# giant-poe-pixel-controller-v1.net
KiCad netlist of a schematic drawn in EAGLE
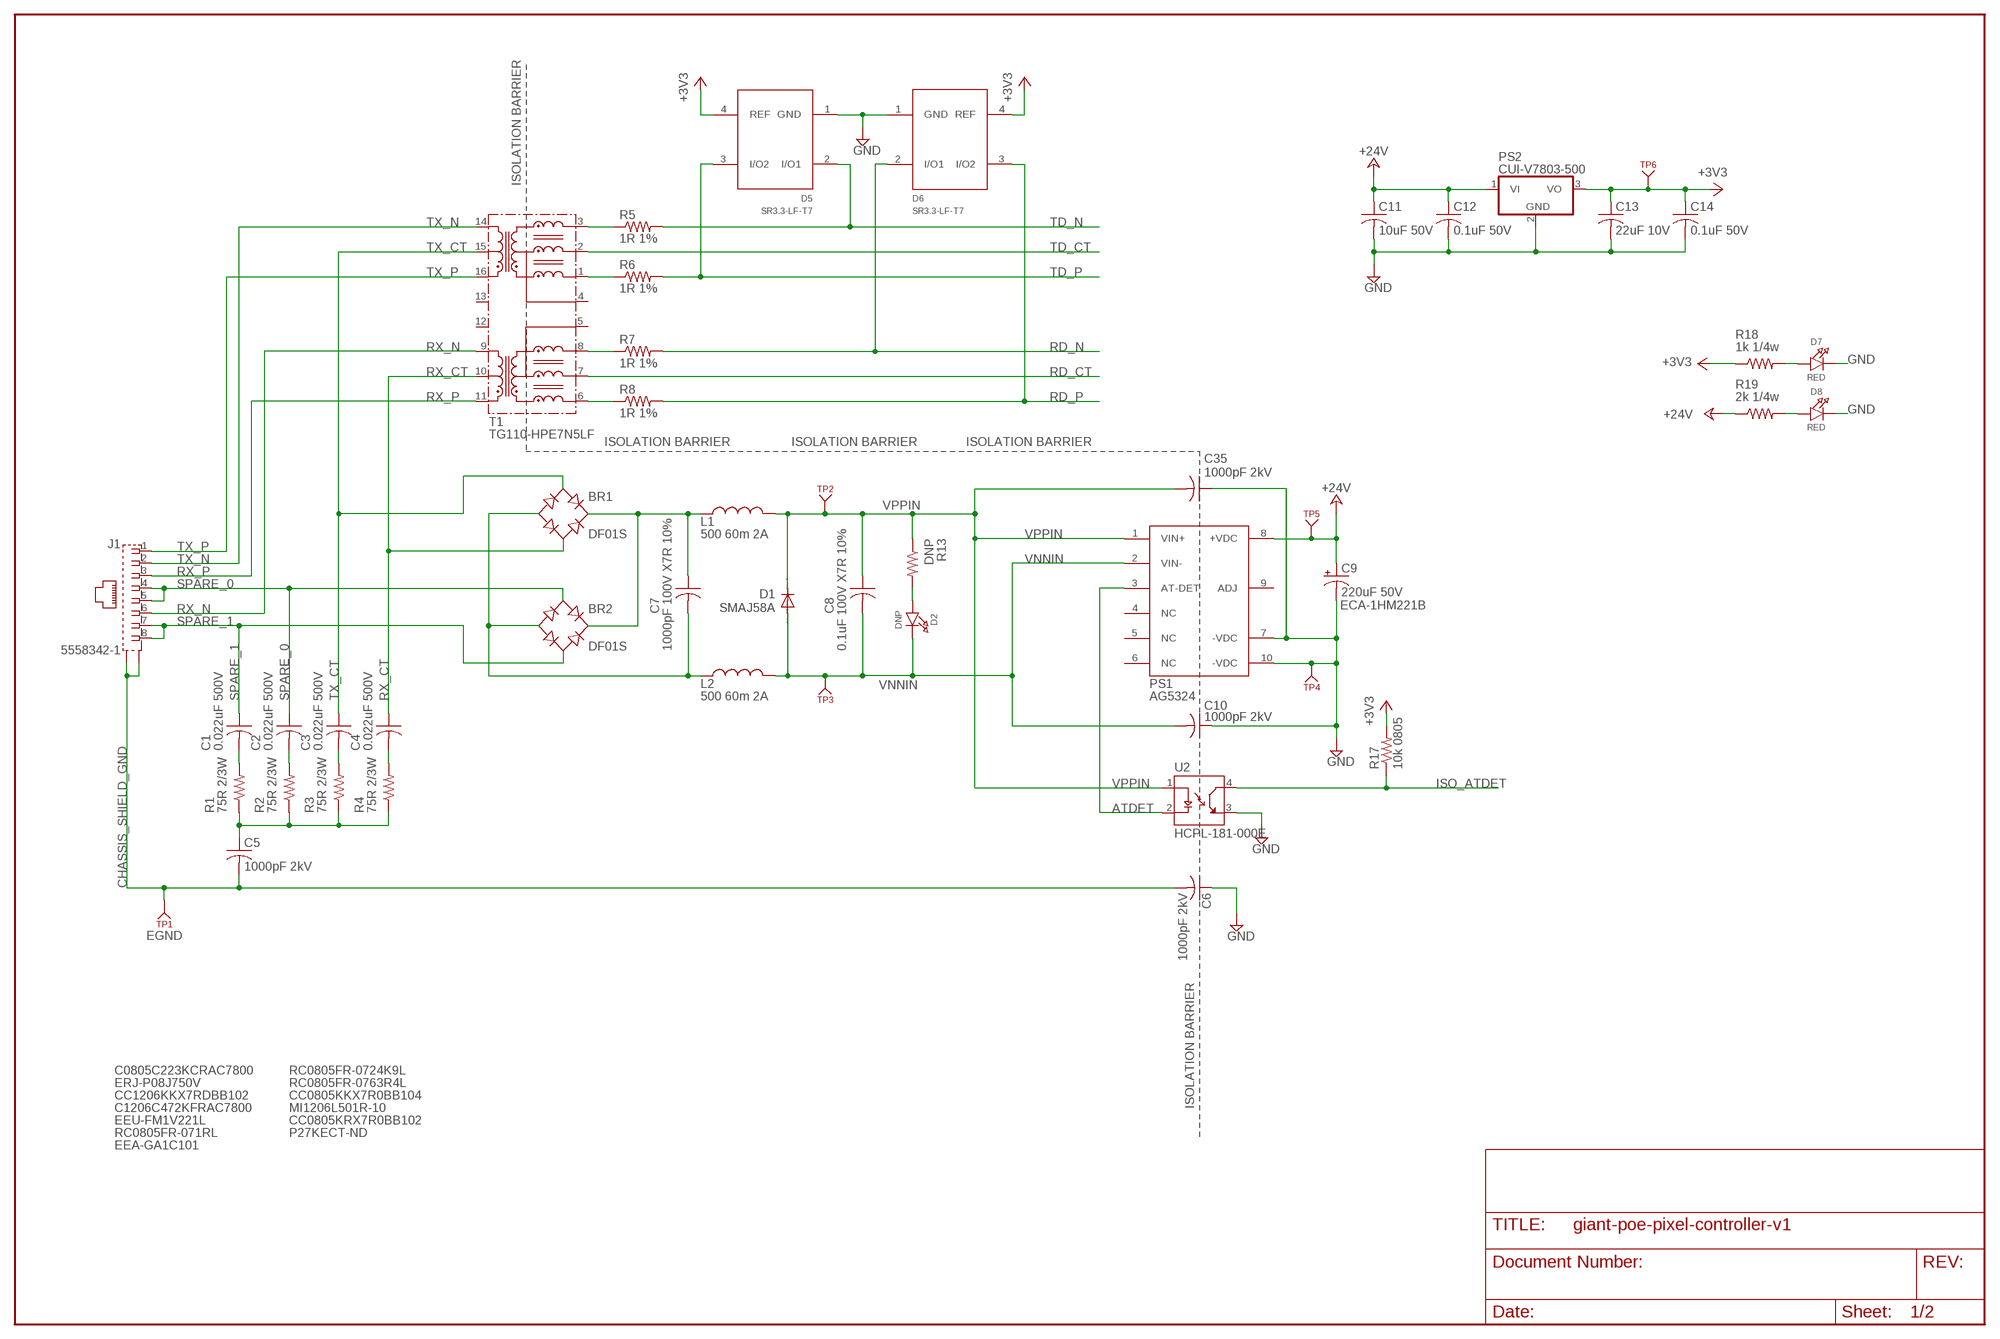
[diagram p0: schematic, sheet 1]
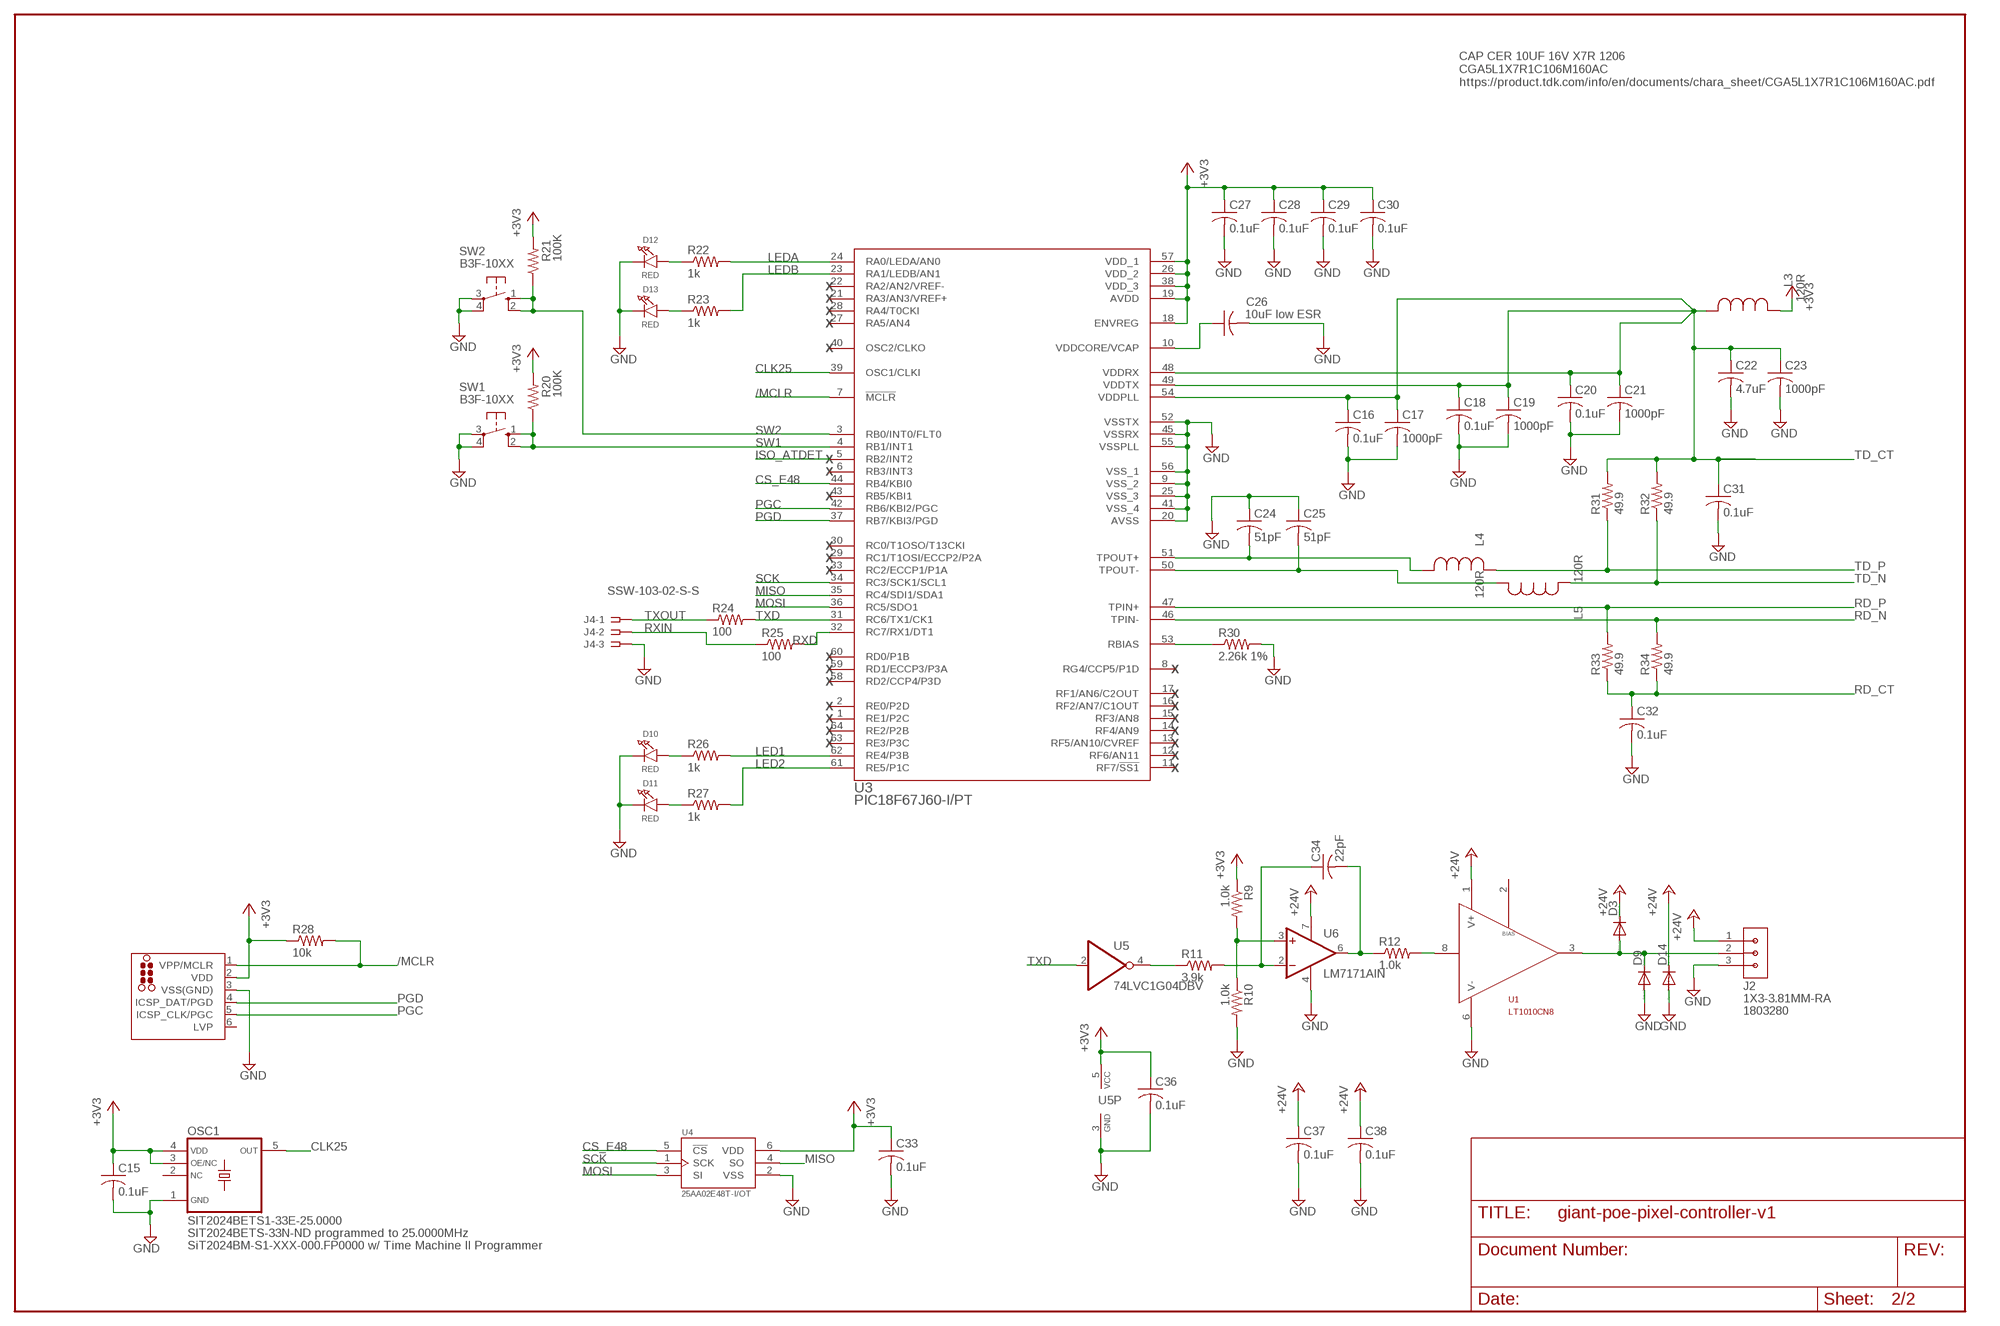
[diagram p1: schematic, sheet 2]

(export (version "E")
  (design (tool "Eeschema 10.0.6"))
  (components
    (comp (ref "BR1")
      (value "DF01S")
      (footprint "eagle-import:DFS")
      (libsource (lib "eagle-import") (part "DFS01"))
    )
    (comp (ref "BR2")
      (value "DF01S")
      (footprint "eagle-import:DFS")
      (libsource (lib "eagle-import") (part "DFS01"))
    )
    (comp (ref "C1")
      (value "0.022uF 500V")
      (footprint "eagle-import:C1206")
      (libsource (lib "eagle-import") (part "C-USC1206"))
    )
    (comp (ref "C2")
      (value "0.022uF 500V")
      (footprint "eagle-import:C1206")
      (libsource (lib "eagle-import") (part "C-USC1206"))
    )
    (comp (ref "C3")
      (value "0.022uF 500V")
      (footprint "eagle-import:C1206")
      (libsource (lib "eagle-import") (part "C-USC1206"))
    )
    (comp (ref "C4")
      (value "0.022uF 500V")
      (footprint "eagle-import:C1206")
      (libsource (lib "eagle-import") (part "C-USC1206"))
    )
    (comp (ref "C5")
      (value "1000pF 2kV")
      (footprint "eagle-import:C1206K")
      (libsource (lib "eagle-import") (part "C-USC1206K"))
    )
    (comp (ref "C6")
      (value "1000pF 2kV")
      (footprint "eagle-import:C1206K")
      (libsource (lib "eagle-import") (part "C-USC1206K"))
    )
    (comp (ref "C7")
      (value "1000pF 100V X7R 10%")
      (footprint "eagle-import:C0805")
      (libsource (lib "eagle-import") (part "C-USC0805"))
    )
    (comp (ref "C8")
      (value "0.1uF 100V X7R 10%")
      (footprint "eagle-import:C0805")
      (libsource (lib "eagle-import") (part "C-USC0805"))
    )
    (comp (ref "C9")
      (value "220uF 50V")
      (footprint "eagle-import:E5-10,5")
      (libsource (lib "eagle-import") (part "CPOL-USE5-10.5"))
    )
    (comp (ref "C10")
      (value "1000pF 2kV")
      (footprint "eagle-import:C1206K")
      (libsource (lib "eagle-import") (part "C-USC1206K"))
    )
    (comp (ref "C11")
      (value "10uF 50V")
      (footprint "eagle-import:C1210K")
      (fields (field (name "MFR") "KEMET") (field (name "MFR_PART_NO") "C1210C106K5RACTU"))
      (libsource (lib "eagle-import") (part "C-USC1210K"))
    )
    (comp (ref "C12")
      (value "0.1uF 50V")
      (footprint "eagle-import:C0805")
      (fields (field (name "MFR") "KEMET") (field (name "MFR_PART_NO") "C1206S104M5RACTU"))
      (libsource (lib "eagle-import") (part "C-USC0805"))
    )
    (comp (ref "C13")
      (value "22uF 10V")
      (footprint "eagle-import:C1206K")
      (fields (field (name "MFR") "KEMET") (field (name "MFR_PART_NO") "C1206C226K8RAC7800"))
      (libsource (lib "eagle-import") (part "C-USC1206K"))
    )
    (comp (ref "C14")
      (value "0.1uF 50V")
      (footprint "eagle-import:C0805")
      (fields (field (name "MFR") "KEMET") (field (name "MFR_PART_NO") "C1206S104M5RACTU"))
      (libsource (lib "eagle-import") (part "C-USC0805"))
    )
    (comp (ref "C35")
      (value "1000pF 2kV")
      (footprint "eagle-import:C1206K")
      (libsource (lib "eagle-import") (part "C-USC1206K"))
    )
    (comp (ref "D1")
      (value "SMAJ58A")
      (footprint "eagle-import:DO214AC")
      (libsource (lib "eagle-import") (part "DIODE-DO214AC"))
    )
    (comp (ref "D2")
      (value "DNP")
      (footprint "eagle-import:CHIPLED_0805_NOOUTLINE")
      (libsource (lib "eagle-import") (part "LED0805_NOOUTLINE"))
    )
    (comp (ref "D5")
      (value "SR3.3-LF-T7")
      (footprint "eagle-import:SOT143B")
      (libsource (lib "eagle-import") (part "SR3.3-LF-T7"))
    )
    (comp (ref "D6")
      (value "SR3.3-LF-T7")
      (footprint "eagle-import:SOT143B")
      (libsource (lib "eagle-import") (part "SR3.3-LF-T7"))
    )
    (comp (ref "D7")
      (value "RED")
      (footprint "eagle-import:CHIPLED_0805_NOOUTLINE")
      (libsource (lib "eagle-import") (part "LED0805_NOOUTLINE"))
    )
    (comp (ref "D8")
      (value "RED")
      (footprint "eagle-import:CHIPLED_0805_NOOUTLINE")
      (libsource (lib "eagle-import") (part "LED0805_NOOUTLINE"))
    )
    (comp (ref "J1")
      (value "5558342-1")
      (footprint "eagle-import:TE_5558342-1")
      (fields (field (name "DIGI-KEY_PART_NUMBER") "A31466-ND") (field (name "MF") "TE Connectivity"))
      (libsource (lib "eagle-import") (part "5558342-1"))
    )
    (comp (ref "L1")
      (value "500 60m 2A")
      (footprint "eagle-import:L3216C")
      (libsource (lib "eagle-import") (part "L-USL3216C"))
    )
    (comp (ref "L2")
      (value "500 60m 2A")
      (footprint "eagle-import:L3216C")
      (libsource (lib "eagle-import") (part "L-USL3216C"))
    )
    (comp (ref "PS1")
      (value "AG5324")
      (footprint "eagle-import:AG5324")
      (libsource (lib "eagle-import") (part "AG5324"))
    )
    (comp (ref "PS2")
      (value "CUI-V7803-500")
      (footprint "eagle-import:CUI-78XX-500")
      (libsource (lib "eagle-import") (part "CUI-V7803-500"))
    )
    (comp (ref "R1")
      (value "75R 2/3W")
      (footprint "eagle-import:R1206")
      (libsource (lib "eagle-import") (part "R-US_R1206"))
    )
    (comp (ref "R2")
      (value "75R 2/3W")
      (footprint "eagle-import:R1206")
      (libsource (lib "eagle-import") (part "R-US_R1206"))
    )
    (comp (ref "R3")
      (value "75R 2/3W")
      (footprint "eagle-import:R1206")
      (libsource (lib "eagle-import") (part "R-US_R1206"))
    )
    (comp (ref "R4")
      (value "75R 2/3W")
      (footprint "eagle-import:R1206")
      (libsource (lib "eagle-import") (part "R-US_R1206"))
    )
    (comp (ref "R5")
      (value "1R 1%")
      (footprint "eagle-import:R0805")
      (libsource (lib "eagle-import") (part "R-US_R0805"))
    )
    (comp (ref "R6")
      (value "1R 1%")
      (footprint "eagle-import:R0805")
      (libsource (lib "eagle-import") (part "R-US_R0805"))
    )
    (comp (ref "R7")
      (value "1R 1%")
      (footprint "eagle-import:R0805")
      (libsource (lib "eagle-import") (part "R-US_R0805"))
    )
    (comp (ref "R8")
      (value "1R 1%")
      (footprint "eagle-import:R0805")
      (libsource (lib "eagle-import") (part "R-US_R0805"))
    )
    (comp (ref "R13")
      (value "DNP")
      (footprint "eagle-import:R1206")
      (libsource (lib "eagle-import") (part "R-US_R1206"))
    )
    (comp (ref "R17")
      (value "10k 0805")
      (footprint "eagle-import:R0805")
      (libsource (lib "eagle-import") (part "resistor_R-US_R0805"))
    )
    (comp (ref "R18")
      (value "1k 1/4w")
      (footprint "eagle-import:R0805")
      (libsource (lib "eagle-import") (part "R-US_R0805"))
    )
    (comp (ref "R19")
      (value "2k 1/4w")
      (footprint "eagle-import:R0805")
      (libsource (lib "eagle-import") (part "R-US_R0805"))
    )
    (comp (ref "T1")
      (value "TG110-HPE7N5LF")
      (footprint "eagle-import:RP-ULTRA")
      (libsource (lib "eagle-import") (part "TG110-HPE7N5LF"))
    )
    (comp (ref "TP1")
      (value "KEYSTONE_500X")
      (footprint "eagle-import:KEYSTONE_TP500X")
      (libsource (lib "eagle-import") (part "KEYSTONE_500X"))
    )
    (comp (ref "TP2")
      (value "KEYSTONE_500X")
      (footprint "eagle-import:KEYSTONE_TP500X")
      (libsource (lib "eagle-import") (part "KEYSTONE_500X"))
    )
    (comp (ref "TP3")
      (value "KEYSTONE_500X")
      (footprint "eagle-import:KEYSTONE_TP500X")
      (libsource (lib "eagle-import") (part "KEYSTONE_500X"))
    )
    (comp (ref "TP4")
      (value "KEYSTONE_500X")
      (footprint "eagle-import:KEYSTONE_TP500X")
      (libsource (lib "eagle-import") (part "KEYSTONE_500X"))
    )
    (comp (ref "TP5")
      (value "KEYSTONE_500X")
      (footprint "eagle-import:KEYSTONE_TP500X")
      (libsource (lib "eagle-import") (part "KEYSTONE_500X"))
    )
    (comp (ref "TP6")
      (value "KEYSTONE_500X")
      (footprint "eagle-import:KEYSTONE_TP500X")
      (libsource (lib "eagle-import") (part "KEYSTONE_500X"))
    )
    (comp (ref "U2")
      (value "HCPL-181-000E")
      (footprint "eagle-import:SOIC254P675X240-4N")
      (fields (field (name "DIGI-KEY_PART_NUMBER") "516-1646-1-ND") (field (name "MF") "Broadcom Limited"))
      (libsource (lib "eagle-import") (part "HCPL-181-000E"))
    )
    (comp (ref "C15")
      (value "0.1uF")
      (footprint "eagle-import:C0603")
      (libsource (lib "eagle-import") (part "C-USC0603"))
    )
    (comp (ref "C16")
      (value "0.1uF")
      (footprint "eagle-import:C0805")
      (libsource (lib "eagle-import") (part "C-USC0805"))
    )
    (comp (ref "C17")
      (value "1000pF")
      (footprint "eagle-import:C0805")
      (libsource (lib "eagle-import") (part "C-USC0805"))
    )
    (comp (ref "C18")
      (value "0.1uF")
      (footprint "eagle-import:C0805")
      (libsource (lib "eagle-import") (part "C-USC0805"))
    )
    (comp (ref "C19")
      (value "1000pF")
      (footprint "eagle-import:C0805")
      (libsource (lib "eagle-import") (part "C-USC0805"))
    )
    (comp (ref "C20")
      (value "0.1uF")
      (footprint "eagle-import:C0805")
      (libsource (lib "eagle-import") (part "C-USC0805"))
    )
    (comp (ref "C21")
      (value "1000pF")
      (footprint "eagle-import:C0805")
      (libsource (lib "eagle-import") (part "C-USC0805"))
    )
    (comp (ref "C22")
      (value "4.7uF")
      (footprint "eagle-import:C0805")
      (libsource (lib "eagle-import") (part "C-USC0805"))
    )
    (comp (ref "C23")
      (value "1000pF")
      (footprint "eagle-import:C0805")
      (libsource (lib "eagle-import") (part "C-USC0805"))
    )
    (comp (ref "C24")
      (value "51pF")
      (footprint "eagle-import:C0805")
      (libsource (lib "eagle-import") (part "C-USC0805"))
    )
    (comp (ref "C25")
      (value "51pF")
      (footprint "eagle-import:C0805")
      (libsource (lib "eagle-import") (part "C-USC0805"))
    )
    (comp (ref "C26")
      (value "10uF low ESR")
      (footprint "eagle-import:C1206")
      (libsource (lib "eagle-import") (part "resistor_C-USC1206"))
    )
    (comp (ref "C27")
      (value "0.1uF")
      (footprint "eagle-import:C0603")
      (libsource (lib "eagle-import") (part "C-USC0603"))
    )
    (comp (ref "C28")
      (value "0.1uF")
      (footprint "eagle-import:C0603")
      (libsource (lib "eagle-import") (part "C-USC0603"))
    )
    (comp (ref "C29")
      (value "0.1uF")
      (footprint "eagle-import:C0603")
      (libsource (lib "eagle-import") (part "C-USC0603"))
    )
    (comp (ref "C30")
      (value "0.1uF")
      (footprint "eagle-import:C0603")
      (libsource (lib "eagle-import") (part "C-USC0603"))
    )
    (comp (ref "C31")
      (value "0.1uF")
      (footprint "eagle-import:C0805")
      (libsource (lib "eagle-import") (part "C-USC0805"))
    )
    (comp (ref "C32")
      (value "0.1uF")
      (footprint "eagle-import:C0805")
      (libsource (lib "eagle-import") (part "C-USC0805"))
    )
    (comp (ref "C33")
      (value "0.1uF")
      (footprint "eagle-import:C0603")
      (libsource (lib "eagle-import") (part "C-USC0603"))
    )
    (comp (ref "C34")
      (value "22pF")
      (footprint "eagle-import:C0805")
      (libsource (lib "eagle-import") (part "C-USC0805"))
    )
    (comp (ref "C36")
      (value "0.1uF")
      (footprint "eagle-import:C0603")
      (libsource (lib "eagle-import") (part "C-USC0603"))
    )
    (comp (ref "C37")
      (value "0.1uF")
      (footprint "eagle-import:C0603")
      (libsource (lib "eagle-import") (part "C-USC0603"))
    )
    (comp (ref "C38")
      (value "0.1uF")
      (footprint "eagle-import:C0603")
      (libsource (lib "eagle-import") (part "C-USC0603"))
    )
    (comp (ref "D3")
      (value "DIODE-SOD123")
      (footprint "eagle-import:SOD123")
      (libsource (lib "eagle-import") (part "DIODE-SOD123"))
    )
    (comp (ref "D9")
      (value "DIODE-SOD123")
      (footprint "eagle-import:SOD123")
      (libsource (lib "eagle-import") (part "DIODE-SOD123"))
    )
    (comp (ref "D10")
      (value "RED")
      (footprint "eagle-import:CHIPLED_0805_NOOUTLINE")
      (libsource (lib "eagle-import") (part "LED0805_NOOUTLINE"))
    )
    (comp (ref "D11")
      (value "RED")
      (footprint "eagle-import:CHIPLED_0805_NOOUTLINE")
      (libsource (lib "eagle-import") (part "LED0805_NOOUTLINE"))
    )
    (comp (ref "D12")
      (value "RED")
      (footprint "eagle-import:CHIPLED_0805_NOOUTLINE")
      (libsource (lib "eagle-import") (part "LED0805_NOOUTLINE"))
    )
    (comp (ref "D13")
      (value "RED")
      (footprint "eagle-import:CHIPLED_0805_NOOUTLINE")
      (libsource (lib "eagle-import") (part "LED0805_NOOUTLINE"))
    )
    (comp (ref "D14")
      (value "DIODE-SOD123")
      (footprint "eagle-import:SOD123")
      (libsource (lib "eagle-import") (part "DIODE-SOD123"))
    )
    (comp (ref "J2")
      (value "1X3-3.81MM-RA")
      (footprint "eagle-import:CON-PHOENIX-3.81-1X3-RA")
      (fields (field (name "MFR") "PHOENIX") (field (name "MFR_PART_NO") "1803280"))
      (libsource (lib "eagle-import") (part "CON-3.81MM-1X3-PHOENIX-RA"))
    )
    (comp (ref "J3")
      (value "TC2030-MCP-NL")
      (footprint "eagle-import:TC2030-MCP-NL")
      (libsource (lib "eagle-import") (part "TC2030-MCP-NL"))
    )
    (comp (ref "J4")
      (value "SSW-103-02-S-S")
      (footprint "eagle-import:SSW-103-02-S-S")
      (libsource (lib "eagle-import") (part "SSW-103-02-S-S"))
    )
    (comp (ref "L3")
      (value "120R")
      (footprint "eagle-import:IND_1608-M")
      (fields (field (name "MANUFACTURER_PART_NUMBER") "MMZ1608B121CTAH0"))
      (libsource (lib "eagle-import") (part "MMZ1608B121CTAH0IND_1608-M"))
    )
    (comp (ref "L4")
      (value "120R")
      (footprint "eagle-import:IND_1608-M")
      (fields (field (name "MANUFACTURER_PART_NUMBER") "MMZ1608B121CTAH0"))
      (libsource (lib "eagle-import") (part "MMZ1608B121CTAH0IND_1608-M"))
    )
    (comp (ref "L5")
      (value "120R")
      (footprint "eagle-import:IND_1608-M")
      (fields (field (name "MANUFACTURER_PART_NUMBER") "MMZ1608B121CTAH0"))
      (libsource (lib "eagle-import") (part "MMZ1608B121CTAH0IND_1608-M"))
    )
    (comp (ref "OSC1")
      (value "SIT2024BETS1-33E-25.0000")
      (footprint "eagle-import:SOT23-5")
      (libsource (lib "eagle-import") (part "SIT2024BETS1-33E-10.0000"))
    )
    (comp (ref "R9")
      (value "1.0k")
      (footprint "eagle-import:R0805")
      (libsource (lib "eagle-import") (part "R-US_R0805"))
    )
    (comp (ref "R10")
      (value "1.0k")
      (footprint "eagle-import:R0805")
      (libsource (lib "eagle-import") (part "R-US_R0805"))
    )
    (comp (ref "R11")
      (value "3.9k")
      (footprint "eagle-import:R0805")
      (libsource (lib "eagle-import") (part "R-US_R0805"))
    )
    (comp (ref "R12")
      (value "1.0k")
      (footprint "eagle-import:R0805")
      (libsource (lib "eagle-import") (part "R-US_R0805"))
    )
    (comp (ref "R20")
      (value "100K")
      (footprint "eagle-import:R0805")
      (libsource (lib "eagle-import") (part "R-US_R0805"))
    )
    (comp (ref "R21")
      (value "100K")
      (footprint "eagle-import:R0805")
      (libsource (lib "eagle-import") (part "R-US_R0805"))
    )
    (comp (ref "R22")
      (value "1k")
      (footprint "eagle-import:R0805")
      (libsource (lib "eagle-import") (part "R-US_R0805"))
    )
    (comp (ref "R23")
      (value "1k")
      (footprint "eagle-import:R0805")
      (libsource (lib "eagle-import") (part "R-US_R0805"))
    )
    (comp (ref "R24")
      (value "100")
      (footprint "eagle-import:R0805")
      (libsource (lib "eagle-import") (part "R-US_R0805"))
    )
    (comp (ref "R25")
      (value "100")
      (footprint "eagle-import:R0805")
      (libsource (lib "eagle-import") (part "R-US_R0805"))
    )
    (comp (ref "R26")
      (value "1k")
      (footprint "eagle-import:R0805")
      (libsource (lib "eagle-import") (part "R-US_R0805"))
    )
    (comp (ref "R27")
      (value "1k")
      (footprint "eagle-import:R0805")
      (libsource (lib "eagle-import") (part "R-US_R0805"))
    )
    (comp (ref "R28")
      (value "10k")
      (footprint "eagle-import:R0805")
      (libsource (lib "eagle-import") (part "R-US_R0805"))
    )
    (comp (ref "R30")
      (value "2.26k 1%")
      (footprint "eagle-import:R0805")
      (libsource (lib "eagle-import") (part "R-US_R0805"))
    )
    (comp (ref "R31")
      (value "49.9")
      (footprint "eagle-import:R0805")
      (libsource (lib "eagle-import") (part "R-US_R0805"))
    )
    (comp (ref "R32")
      (value "49.9")
      (footprint "eagle-import:R0805")
      (libsource (lib "eagle-import") (part "R-US_R0805"))
    )
    (comp (ref "R33")
      (value "49.9")
      (footprint "eagle-import:R0805")
      (libsource (lib "eagle-import") (part "R-US_R0805"))
    )
    (comp (ref "R34")
      (value "49.9")
      (footprint "eagle-import:R0805")
      (libsource (lib "eagle-import") (part "R-US_R0805"))
    )
    (comp (ref "SW1")
      (value "B3F-10XX")
      (footprint "eagle-import:B3F-10XX")
      (libsource (lib "eagle-import") (part "10-XX"))
    )
    (comp (ref "SW2")
      (value "B3F-10XX")
      (footprint "eagle-import:B3F-10XX")
      (libsource (lib "eagle-import") (part "10-XX"))
    )
    (comp (ref "U1")
      (value "LT1010CN8")
      (footprint "eagle-import:DIL08")
      (libsource (lib "eagle-import") (part "LT1010CN8"))
    )
    (comp (ref "U3")
      (value "PIC18F67J60-I/PT")
      (footprint "eagle-import:TQFP64_10X10MC")
      (fields (field (name "MANUFACTURER_PART_NUMBER") "PIC18F67J60IPT"))
      (libsource (lib "eagle-import") (part "PIC18F67J60-I/PT"))
    )
    (comp (ref "U4")
      (value "25AA02E48T-I/OT")
      (footprint "eagle-import:SOT95P270X145-6N")
      (fields (field (name "DIGI-KEY_PART_NUMBER") "25AA02E48T-I/OTCT-ND") (field (name "MF") "Microchip"))
      (libsource (lib "eagle-import") (part "25AA02E48T-I/OT"))
    )
    (comp (ref "U5")
      (value "74LVC1G04DBV")
      (footprint "eagle-import:SOT23-5")
      (libsource (lib "eagle-import") (part "741G04DBVLVC"))
    )
    (comp (ref "U6")
      (value "LM7171AIN")
      (footprint "eagle-import:SO08")
      (libsource (lib "eagle-import") (part "LM307D"))
    )
  )
  (nets
    (net (code "1") (name "+3V3") (class "Default")
      (node (ref "C13") (pin "1") (pinfunction "1_1") (pintype "passive"))
      (node (ref "C14") (pin "1") (pinfunction "1_1") (pintype "passive"))
      (node (ref "C15") (pin "1") (pinfunction "1_1") (pintype "passive"))
      (node (ref "C27") (pin "1") (pinfunction "1_1") (pintype "passive"))
      (node (ref "C28") (pin "1") (pinfunction "1_1") (pintype "passive"))
      (node (ref "C29") (pin "1") (pinfunction "1_1") (pintype "passive"))
      (node (ref "C30") (pin "1") (pinfunction "1_1") (pintype "passive"))
      (node (ref "C33") (pin "1") (pinfunction "1_1") (pintype "passive"))
      (node (ref "C36") (pin "1") (pinfunction "1_1") (pintype "passive"))
      (node (ref "D5") (pin "4") (pinfunction "REF_4") (pintype "bidirectional"))
      (node (ref "D6") (pin "4") (pinfunction "REF_4") (pintype "bidirectional"))
      (node (ref "J3") (pin "2") (pinfunction "VDD_2") (pintype "power_in"))
      (node (ref "L3") (pin "2") (pinfunction "2_2") (pintype "passive"))
      (node (ref "OSC1") (pin "3") (pinfunction "OE/NC_3") (pintype "bidirectional"))
      (node (ref "OSC1") (pin "4") (pinfunction "VDD_4") (pintype "bidirectional"))
      (node (ref "PS2") (pin "3") (pinfunction "VO_3") (pintype "passive"))
      (node (ref "R17") (pin "2") (pinfunction "2_2") (pintype "passive"))
      (node (ref "R18") (pin "1") (pinfunction "1_1") (pintype "passive"))
      (node (ref "R20") (pin "2") (pinfunction "2_2") (pintype "passive"))
      (node (ref "R21") (pin "2") (pinfunction "2_2") (pintype "passive"))
      (node (ref "R28") (pin "1") (pinfunction "1_1") (pintype "passive"))
      (node (ref "R9") (pin "1") (pinfunction "1_1") (pintype "passive"))
      (node (ref "TP6") (pin "1") (pinfunction "P$1_1") (pintype "bidirectional"))
      (node (ref "U3") (pin "18") (pinfunction "ENVREG_18") (pintype "passive"))
      (node (ref "U3") (pin "19") (pinfunction "AVDD_19") (pintype "passive"))
      (node (ref "U3") (pin "26") (pinfunction "VDD_2_26") (pintype "passive"))
      (node (ref "U3") (pin "38") (pinfunction "VDD_3_38") (pintype "passive"))
      (node (ref "U3") (pin "57") (pinfunction "VDD_1_57") (pintype "passive"))
      (node (ref "U4") (pin "6") (pinfunction "VDD_6") (pintype "power_in"))
      (node (ref "U5") (pin "5") (pinfunction "VCC_5") (pintype "power_in"))
    )
    (net (code "2") (name "+24V") (class "Default")
      (node (ref "C11") (pin "1") (pinfunction "1_1") (pintype "passive"))
      (node (ref "C12") (pin "1") (pinfunction "1_1") (pintype "passive"))
      (node (ref "C37") (pin "1") (pinfunction "1_1") (pintype "passive"))
      (node (ref "C38") (pin "1") (pinfunction "1_1") (pintype "passive"))
      (node (ref "C9") (pin "+") (pinfunction "+_+") (pintype "passive"))
      (node (ref "D14") (pin "C") (pinfunction "C_C") (pintype "passive"))
      (node (ref "D3") (pin "C") (pinfunction "C_C") (pintype "passive"))
      (node (ref "J2") (pin "1") (pinfunction "1_1") (pintype "bidirectional"))
      (node (ref "PS1") (pin "8") (pinfunction "+VDC_8") (pintype "bidirectional"))
      (node (ref "PS2") (pin "1") (pinfunction "VI_1") (pintype "input"))
      (node (ref "R19") (pin "1") (pinfunction "1_1") (pintype "passive"))
      (node (ref "TP5") (pin "1") (pinfunction "P$1_1") (pintype "bidirectional"))
      (node (ref "U1") (pin "1") (pinfunction "V+_1") (pintype "bidirectional"))
      (node (ref "U6") (pin "7") (pinfunction "V+_7") (pintype "power_in"))
    )
    (net (code "3") (name "ATDET") (class "Default")
      (node (ref "PS1") (pin "3") (pinfunction "AT-DET_3") (pintype "bidirectional"))
      (node (ref "U2") (pin "2") (pinfunction "CATHODE_2") (pintype "passive"))
    )
    (net (code "4") (name "CHASSIS_SHIELD_GND") (class "Default")
      (node (ref "C5") (pin "2") (pinfunction "2_2") (pintype "passive"))
      (node (ref "C6") (pin "2") (pinfunction "2_2") (pintype "passive"))
      (node (ref "J1") (pin "SH1") (pinfunction "S1_SH1") (pintype "passive"))
      (node (ref "J1") (pin "SH2") (pinfunction "S2_SH2") (pintype "passive"))
      (node (ref "TP1") (pin "1") (pinfunction "P$1_1") (pintype "bidirectional"))
    )
    (net (code "5") (name "CLK25") (class "Default")
      (node (ref "OSC1") (pin "5") (pinfunction "OUT_5") (pintype "bidirectional"))
      (node (ref "U3") (pin "39") (pinfunction "OSC1/CLKI_39") (pintype "passive"))
    )
    (net (code "6") (name "CS_E48") (class "Default")
      (node (ref "U3") (pin "44") (pinfunction "RB4/KBI0_44") (pintype "passive"))
      (node (ref "U4") (pin "5") (pinfunction "~{CS}_5") (pintype "input"))
    )
    (net (code "7") (name "GND") (class "Default")
      (node (ref "C10") (pin "1") (pinfunction "1_1") (pintype "passive"))
      (node (ref "C11") (pin "2") (pinfunction "2_2") (pintype "passive"))
      (node (ref "C12") (pin "2") (pinfunction "2_2") (pintype "passive"))
      (node (ref "C13") (pin "2") (pinfunction "2_2") (pintype "passive"))
      (node (ref "C14") (pin "2") (pinfunction "2_2") (pintype "passive"))
      (node (ref "C15") (pin "2") (pinfunction "2_2") (pintype "passive"))
      (node (ref "C16") (pin "2") (pinfunction "2_2") (pintype "passive"))
      (node (ref "C17") (pin "2") (pinfunction "2_2") (pintype "passive"))
      (node (ref "C18") (pin "2") (pinfunction "2_2") (pintype "passive"))
      (node (ref "C19") (pin "2") (pinfunction "2_2") (pintype "passive"))
      (node (ref "C20") (pin "2") (pinfunction "2_2") (pintype "passive"))
      (node (ref "C21") (pin "2") (pinfunction "2_2") (pintype "passive"))
      (node (ref "C22") (pin "2") (pinfunction "2_2") (pintype "passive"))
      (node (ref "C23") (pin "2") (pinfunction "2_2") (pintype "passive"))
      (node (ref "C24") (pin "1") (pinfunction "1_1") (pintype "passive"))
      (node (ref "C25") (pin "1") (pinfunction "1_1") (pintype "passive"))
      (node (ref "C26") (pin "2") (pinfunction "2_2") (pintype "passive"))
      (node (ref "C27") (pin "2") (pinfunction "2_2") (pintype "passive"))
      (node (ref "C28") (pin "2") (pinfunction "2_2") (pintype "passive"))
      (node (ref "C29") (pin "2") (pinfunction "2_2") (pintype "passive"))
      (node (ref "C30") (pin "2") (pinfunction "2_2") (pintype "passive"))
      (node (ref "C31") (pin "2") (pinfunction "2_2") (pintype "passive"))
      (node (ref "C32") (pin "2") (pinfunction "2_2") (pintype "passive"))
      (node (ref "C33") (pin "2") (pinfunction "2_2") (pintype "passive"))
      (node (ref "C35") (pin "1") (pinfunction "1_1") (pintype "passive"))
      (node (ref "C36") (pin "2") (pinfunction "2_2") (pintype "passive"))
      (node (ref "C37") (pin "2") (pinfunction "2_2") (pintype "passive"))
      (node (ref "C38") (pin "2") (pinfunction "2_2") (pintype "passive"))
      (node (ref "C6") (pin "1") (pinfunction "1_1") (pintype "passive"))
      (node (ref "C9") (pin "-") (pinfunction "-_-") (pintype "passive"))
      (node (ref "D10") (pin "C") (pinfunction "C_C") (pintype "passive"))
      (node (ref "D11") (pin "C") (pinfunction "C_C") (pintype "passive"))
      (node (ref "D12") (pin "C") (pinfunction "C_C") (pintype "passive"))
      (node (ref "D13") (pin "C") (pinfunction "C_C") (pintype "passive"))
      (node (ref "D14") (pin "A") (pinfunction "A_A") (pintype "passive"))
      (node (ref "D5") (pin "1") (pinfunction "GND_1") (pintype "bidirectional"))
      (node (ref "D6") (pin "1") (pinfunction "GND_1") (pintype "bidirectional"))
      (node (ref "D7") (pin "C") (pinfunction "C_C") (pintype "passive"))
      (node (ref "D8") (pin "C") (pinfunction "C_C") (pintype "passive"))
      (node (ref "D9") (pin "A") (pinfunction "A_A") (pintype "passive"))
      (node (ref "J2") (pin "3") (pinfunction "3_3") (pintype "bidirectional"))
      (node (ref "J3") (pin "3") (pinfunction "VSS(GND)_3") (pintype "power_in"))
      (node (ref "J4") (pin "3") (pinfunction "1_3") (pintype "passive"))
      (node (ref "OSC1") (pin "1") (pinfunction "GND_1") (pintype "bidirectional"))
      (node (ref "PS1") (pin "10") (pinfunction "-VDC_10") (pintype "bidirectional"))
      (node (ref "PS1") (pin "7") (pinfunction "-VDC_7") (pintype "bidirectional"))
      (node (ref "PS2") (pin "2") (pinfunction "GND_2") (pintype "passive"))
      (node (ref "R10") (pin "2") (pinfunction "2_2") (pintype "passive"))
      (node (ref "R30") (pin "2") (pinfunction "2_2") (pintype "passive"))
      (node (ref "SW1") (pin "3") (pinfunction "P_3") (pintype "passive"))
      (node (ref "SW1") (pin "4") (pinfunction "P1_4") (pintype "passive"))
      (node (ref "SW2") (pin "3") (pinfunction "P_3") (pintype "passive"))
      (node (ref "SW2") (pin "4") (pinfunction "P1_4") (pintype "passive"))
      (node (ref "TP4") (pin "1") (pinfunction "P$1_1") (pintype "bidirectional"))
      (node (ref "U1") (pin "6") (pinfunction "V-_6") (pintype "bidirectional"))
      (node (ref "U2") (pin "3") (pinfunction "EMITTER_3") (pintype "passive"))
      (node (ref "U3") (pin "20") (pinfunction "AVSS_20") (pintype "passive"))
      (node (ref "U3") (pin "25") (pinfunction "VSS_3_25") (pintype "passive"))
      (node (ref "U3") (pin "41") (pinfunction "VSS_4_41") (pintype "passive"))
      (node (ref "U3") (pin "45") (pinfunction "VSSRX_45") (pintype "passive"))
      (node (ref "U3") (pin "52") (pinfunction "VSSTX_52") (pintype "passive"))
      (node (ref "U3") (pin "55") (pinfunction "VSSPLL_55") (pintype "passive"))
      (node (ref "U3") (pin "56") (pinfunction "VSS_1_56") (pintype "passive"))
      (node (ref "U3") (pin "9") (pinfunction "VSS_2_9") (pintype "passive"))
      (node (ref "U4") (pin "2") (pinfunction "VSS_2") (pintype "power_in"))
      (node (ref "U5") (pin "3") (pinfunction "GND_3") (pintype "power_in"))
      (node (ref "U6") (pin "4") (pinfunction "V-_4") (pintype "power_in"))
    )
    (net (code "8") (name "ISO_ATDET") (class "Default")
      (node (ref "R17") (pin "1") (pinfunction "1_1") (pintype "passive"))
      (node (ref "U2") (pin "4") (pinfunction "COLLECTOR_4") (pintype "passive"))
      (node (ref "U3") (pin "5") (pinfunction "RB2/INT2_5") (pintype "passive"))
    )
    (net (code "9") (name "LED1") (class "Default")
      (node (ref "R26") (pin "2") (pinfunction "2_2") (pintype "passive"))
      (node (ref "U3") (pin "62") (pinfunction "RE4/P3B_62") (pintype "passive"))
    )
    (net (code "10") (name "LED2") (class "Default")
      (node (ref "R27") (pin "2") (pinfunction "2_2") (pintype "passive"))
      (node (ref "U3") (pin "61") (pinfunction "RE5/P1C_61") (pintype "passive"))
    )
    (net (code "11") (name "LEDA") (class "Default")
      (node (ref "R22") (pin "2") (pinfunction "2_2") (pintype "passive"))
      (node (ref "U3") (pin "24") (pinfunction "RA0/LEDA/AN0_24") (pintype "passive"))
    )
    (net (code "12") (name "LEDB") (class "Default")
      (node (ref "R23") (pin "2") (pinfunction "2_2") (pintype "passive"))
      (node (ref "U3") (pin "23") (pinfunction "RA1/LEDB/AN1_23") (pintype "passive"))
    )
    (net (code "13") (name "MISO") (class "Default")
      (node (ref "U3") (pin "35") (pinfunction "RC4/SDI1/SDA1_35") (pintype "passive"))
      (node (ref "U4") (pin "4") (pinfunction "SO_4") (pintype "output"))
    )
    (net (code "14") (name "MOSI") (class "Default")
      (node (ref "U3") (pin "36") (pinfunction "RC5/SDO1_36") (pintype "passive"))
      (node (ref "U4") (pin "3") (pinfunction "SI_3") (pintype "input"))
    )
    (net (code "15") (name "Net-(BR1-Pad+)") (class "Default")
      (node (ref "BR1") (pin "+") (pinfunction "+_+") (pintype "passive"))
      (node (ref "BR2") (pin "+") (pinfunction "+_+") (pintype "passive"))
      (node (ref "C7") (pin "1") (pinfunction "1_1") (pintype "passive"))
      (node (ref "L1") (pin "1") (pinfunction "1_1") (pintype "passive"))
    )
    (net (code "16") (name "Net-(BR1-Pad-)") (class "Default")
      (node (ref "BR1") (pin "-") (pinfunction "-_-") (pintype "passive"))
      (node (ref "BR2") (pin "-") (pinfunction "-_-") (pintype "passive"))
      (node (ref "C7") (pin "2") (pinfunction "2_2") (pintype "passive"))
      (node (ref "L2") (pin "1") (pinfunction "1_1") (pintype "passive"))
    )
    (net (code "17") (name "Net-(C1-Pad2)") (class "Default")
      (node (ref "C1") (pin "2") (pinfunction "2_2") (pintype "passive"))
      (node (ref "R1") (pin "2") (pinfunction "2_2") (pintype "passive"))
    )
    (net (code "18") (name "Net-(C2-Pad2)") (class "Default")
      (node (ref "C2") (pin "2") (pinfunction "2_2") (pintype "passive"))
      (node (ref "R2") (pin "2") (pinfunction "2_2") (pintype "passive"))
    )
    (net (code "19") (name "Net-(C3-Pad2)") (class "Default")
      (node (ref "C3") (pin "2") (pinfunction "2_2") (pintype "passive"))
      (node (ref "R3") (pin "2") (pinfunction "2_2") (pintype "passive"))
    )
    (net (code "20") (name "Net-(C4-Pad2)") (class "Default")
      (node (ref "C4") (pin "2") (pinfunction "2_2") (pintype "passive"))
      (node (ref "R4") (pin "2") (pinfunction "2_2") (pintype "passive"))
    )
    (net (code "21") (name "Net-(C5-Pad1)") (class "Default")
      (node (ref "C5") (pin "1") (pinfunction "1_1") (pintype "passive"))
      (node (ref "R1") (pin "1") (pinfunction "1_1") (pintype "passive"))
      (node (ref "R2") (pin "1") (pinfunction "1_1") (pintype "passive"))
      (node (ref "R3") (pin "1") (pinfunction "1_1") (pintype "passive"))
      (node (ref "R4") (pin "1") (pinfunction "1_1") (pintype "passive"))
    )
    (net (code "22") (name "Net-(D2-PadA)") (class "Default")
      (node (ref "D2") (pin "A") (pinfunction "A_A") (pintype "passive"))
      (node (ref "R13") (pin "2") (pinfunction "2_2") (pintype "passive"))
    )
    (net (code "23") (name "Net-(D7-PadA)") (class "Default")
      (node (ref "D7") (pin "A") (pinfunction "A_A") (pintype "passive"))
      (node (ref "R18") (pin "2") (pinfunction "2_2") (pintype "passive"))
    )
    (net (code "24") (name "Net-(D8-PadA)") (class "Default")
      (node (ref "D8") (pin "A") (pinfunction "A_A") (pintype "passive"))
      (node (ref "R19") (pin "2") (pinfunction "2_2") (pintype "passive"))
    )
    (net (code "25") (name "Net-(D10-PadA)") (class "Default")
      (node (ref "D10") (pin "A") (pinfunction "A_A") (pintype "passive"))
      (node (ref "R26") (pin "1") (pinfunction "1_1") (pintype "passive"))
    )
    (net (code "26") (name "Net-(D11-PadA)") (class "Default")
      (node (ref "D11") (pin "A") (pinfunction "A_A") (pintype "passive"))
      (node (ref "R27") (pin "1") (pinfunction "1_1") (pintype "passive"))
    )
    (net (code "27") (name "Net-(D12-PadA)") (class "Default")
      (node (ref "D12") (pin "A") (pinfunction "A_A") (pintype "passive"))
      (node (ref "R22") (pin "1") (pinfunction "1_1") (pintype "passive"))
    )
    (net (code "28") (name "Net-(D13-PadA)") (class "Default")
      (node (ref "D13") (pin "A") (pinfunction "A_A") (pintype "passive"))
      (node (ref "R23") (pin "1") (pinfunction "1_1") (pintype "passive"))
    )
    (net (code "29") (name "Net-(R5-Pad1)") (class "Default")
      (node (ref "R5") (pin "1") (pinfunction "1_1") (pintype "passive"))
      (node (ref "T1") (pin "3") (pinfunction "3_3") (pintype "passive"))
    )
    (net (code "30") (name "Net-(R6-Pad1)") (class "Default")
      (node (ref "R6") (pin "1") (pinfunction "1_1") (pintype "passive"))
      (node (ref "T1") (pin "1") (pinfunction "1_1") (pintype "passive"))
    )
    (net (code "31") (name "Net-(R7-Pad1)") (class "Default")
      (node (ref "R7") (pin "1") (pinfunction "1_1") (pintype "passive"))
      (node (ref "T1") (pin "8") (pinfunction "8_8") (pintype "passive"))
    )
    (net (code "32") (name "Net-(R8-Pad1)") (class "Default")
      (node (ref "R8") (pin "1") (pinfunction "1_1") (pintype "passive"))
      (node (ref "T1") (pin "6") (pinfunction "6_6") (pintype "passive"))
    )
    (net (code "33") (name "Net-(U1-INPUT)") (class "Default")
      (node (ref "R12") (pin "2") (pinfunction "2_2") (pintype "passive"))
      (node (ref "U1") (pin "8") (pinfunction "INPUT_8") (pintype "bidirectional"))
    )
    (net (code "34") (name "Net-(U1-OUTPUT)") (class "Default")
      (node (ref "D3") (pin "A") (pinfunction "A_A") (pintype "passive"))
      (node (ref "D9") (pin "C") (pinfunction "C_C") (pintype "passive"))
      (node (ref "J2") (pin "2") (pinfunction "2_2") (pintype "bidirectional"))
      (node (ref "U1") (pin "3") (pinfunction "OUTPUT_3") (pintype "bidirectional"))
    )
    (net (code "35") (name "Net-(U3-RBIAS)") (class "Default")
      (node (ref "R30") (pin "1") (pinfunction "1_1") (pintype "passive"))
      (node (ref "U3") (pin "53") (pinfunction "RBIAS_53") (pintype "passive"))
    )
    (net (code "36") (name "Net-(U3-TPOUT+)") (class "Default")
      (node (ref "C24") (pin "2") (pinfunction "2_2") (pintype "passive"))
      (node (ref "L4") (pin "1") (pinfunction "1_1") (pintype "passive"))
      (node (ref "U3") (pin "51") (pinfunction "TPOUT+_51") (pintype "passive"))
    )
    (net (code "37") (name "Net-(U3-TPOUT-)") (class "Default")
      (node (ref "C25") (pin "2") (pinfunction "2_2") (pintype "passive"))
      (node (ref "L5") (pin "1") (pinfunction "1_1") (pintype "passive"))
      (node (ref "U3") (pin "50") (pinfunction "TPOUT-_50") (pintype "passive"))
    )
    (net (code "38") (name "Net-(U3-VDDCORE{slash}VCAP)") (class "Default")
      (node (ref "C26") (pin "1") (pinfunction "1_1") (pintype "passive"))
      (node (ref "U3") (pin "10") (pinfunction "VDDCORE/VCAP_10") (pintype "passive"))
    )
    (net (code "39") (name "Net-(U5A-O)") (class "Default")
      (node (ref "R11") (pin "1") (pinfunction "1_1") (pintype "passive"))
      (node (ref "U5") (pin "4") (pinfunction "O_4") (pintype "output"))
    )
    (net (code "40") (name "Net-(U6-+IN)") (class "Default")
      (node (ref "R10") (pin "1") (pinfunction "1_1") (pintype "passive"))
      (node (ref "R9") (pin "2") (pinfunction "2_2") (pintype "passive"))
      (node (ref "U6") (pin "3") (pinfunction "+IN_3") (pintype "input"))
    )
    (net (code "41") (name "Net-(U6--IN)") (class "Default")
      (node (ref "C34") (pin "1") (pinfunction "1_1") (pintype "passive"))
      (node (ref "R11") (pin "2") (pinfunction "2_2") (pintype "passive"))
      (node (ref "U6") (pin "2") (pinfunction "-IN_2") (pintype "input"))
    )
    (net (code "42") (name "Net-(U6-OUT)") (class "Default")
      (node (ref "C34") (pin "2") (pinfunction "2_2") (pintype "passive"))
      (node (ref "R12") (pin "1") (pinfunction "1_1") (pintype "passive"))
      (node (ref "U6") (pin "6") (pinfunction "OUT_6") (pintype "output"))
    )
    (net (code "43") (name "PGC") (class "Default")
      (node (ref "J3") (pin "5") (pinfunction "ICSP_CLK/PGC_5") (pintype "output"))
      (node (ref "U3") (pin "42") (pinfunction "RB6/KBI2/PGC_42") (pintype "passive"))
    )
    (net (code "44") (name "PGD") (class "Default")
      (node (ref "J3") (pin "4") (pinfunction "ICSP_DAT/PGD_4") (pintype "bidirectional"))
      (node (ref "U3") (pin "37") (pinfunction "RB7/KBI3/PGD_37") (pintype "passive"))
    )
    (net (code "45") (name "RD_CT") (class "Default")
      (node (ref "C32") (pin "1") (pinfunction "1_1") (pintype "passive"))
      (node (ref "R33") (pin "1") (pinfunction "1_1") (pintype "passive"))
      (node (ref "R34") (pin "1") (pinfunction "1_1") (pintype "passive"))
      (node (ref "T1") (pin "7") (pinfunction "7_7") (pintype "passive"))
    )
    (net (code "46") (name "RD_N") (class "Default")
      (node (ref "D6") (pin "2") (pinfunction "I/O1_2") (pintype "bidirectional"))
      (node (ref "R34") (pin "2") (pinfunction "2_2") (pintype "passive"))
      (node (ref "R7") (pin "2") (pinfunction "2_2") (pintype "passive"))
      (node (ref "U3") (pin "46") (pinfunction "TPIN-_46") (pintype "passive"))
    )
    (net (code "47") (name "RD_P") (class "Default")
      (node (ref "D6") (pin "3") (pinfunction "I/O2_3") (pintype "bidirectional"))
      (node (ref "R33") (pin "2") (pinfunction "2_2") (pintype "passive"))
      (node (ref "R8") (pin "2") (pinfunction "2_2") (pintype "passive"))
      (node (ref "U3") (pin "47") (pinfunction "TPIN+_47") (pintype "passive"))
    )
    (net (code "48") (name "RXD") (class "Default")
      (node (ref "R25") (pin "2") (pinfunction "2_2") (pintype "passive"))
      (node (ref "U3") (pin "32") (pinfunction "RC7/RX1/DT1_32") (pintype "passive"))
    )
    (net (code "49") (name "RXIN") (class "Default")
      (node (ref "J4") (pin "2") (pinfunction "1_2") (pintype "passive"))
      (node (ref "R25") (pin "1") (pinfunction "1_1") (pintype "passive"))
    )
    (net (code "50") (name "RX_CT") (class "Default")
      (node (ref "BR1") (pin "AC2") (pinfunction "AC2_AC2") (pintype "passive"))
      (node (ref "C4") (pin "1") (pinfunction "1_1") (pintype "passive"))
      (node (ref "T1") (pin "10") (pinfunction "10_10") (pintype "passive"))
    )
    (net (code "51") (name "RX_N") (class "Default")
      (node (ref "J1") (pin "6") (pinfunction "6_6") (pintype "passive"))
      (node (ref "T1") (pin "9") (pinfunction "9_9") (pintype "passive"))
    )
    (net (code "52") (name "RX_P") (class "Default")
      (node (ref "J1") (pin "3") (pinfunction "3_3") (pintype "passive"))
      (node (ref "T1") (pin "11") (pinfunction "11_11") (pintype "passive"))
    )
    (net (code "53") (name "SCK") (class "Default")
      (node (ref "U3") (pin "34") (pinfunction "RC3/SCK1/SCL1_34") (pintype "passive"))
      (node (ref "U4") (pin "1") (pinfunction "SCK_1") (pintype "input"))
    )
    (net (code "54") (name "SPARE_0") (class "Default")
      (node (ref "BR2") (pin "AC1") (pinfunction "AC1_AC1") (pintype "passive"))
      (node (ref "C2") (pin "1") (pinfunction "1_1") (pintype "passive"))
      (node (ref "J1") (pin "4") (pinfunction "4_4") (pintype "passive"))
      (node (ref "J1") (pin "5") (pinfunction "5_5") (pintype "passive"))
    )
    (net (code "55") (name "SPARE_1") (class "Default")
      (node (ref "BR2") (pin "AC2") (pinfunction "AC2_AC2") (pintype "passive"))
      (node (ref "C1") (pin "1") (pinfunction "1_1") (pintype "passive"))
      (node (ref "J1") (pin "7") (pinfunction "7_7") (pintype "passive"))
      (node (ref "J1") (pin "8") (pinfunction "8_8") (pintype "passive"))
    )
    (net (code "56") (name "SW1") (class "Default")
      (node (ref "R20") (pin "1") (pinfunction "1_1") (pintype "passive"))
      (node (ref "SW1") (pin "1") (pinfunction "S_1") (pintype "passive"))
      (node (ref "SW1") (pin "2") (pinfunction "S1_2") (pintype "passive"))
      (node (ref "U3") (pin "4") (pinfunction "RB1/INT1_4") (pintype "passive"))
    )
    (net (code "57") (name "SW2") (class "Default")
      (node (ref "R21") (pin "1") (pinfunction "1_1") (pintype "passive"))
      (node (ref "SW2") (pin "1") (pinfunction "S_1") (pintype "passive"))
      (node (ref "SW2") (pin "2") (pinfunction "S1_2") (pintype "passive"))
      (node (ref "U3") (pin "3") (pinfunction "RB0/INT0/FLT0_3") (pintype "passive"))
    )
    (net (code "58") (name "TD_CT") (class "Default")
      (node (ref "C16") (pin "1") (pinfunction "1_1") (pintype "passive"))
      (node (ref "C17") (pin "1") (pinfunction "1_1") (pintype "passive"))
      (node (ref "C18") (pin "1") (pinfunction "1_1") (pintype "passive"))
      (node (ref "C19") (pin "1") (pinfunction "1_1") (pintype "passive"))
      (node (ref "C20") (pin "1") (pinfunction "1_1") (pintype "passive"))
      (node (ref "C21") (pin "1") (pinfunction "1_1") (pintype "passive"))
      (node (ref "C22") (pin "1") (pinfunction "1_1") (pintype "passive"))
      (node (ref "C23") (pin "1") (pinfunction "1_1") (pintype "passive"))
      (node (ref "C31") (pin "1") (pinfunction "1_1") (pintype "passive"))
      (node (ref "L3") (pin "1") (pinfunction "1_1") (pintype "passive"))
      (node (ref "R31") (pin "2") (pinfunction "2_2") (pintype "passive"))
      (node (ref "R32") (pin "2") (pinfunction "2_2") (pintype "passive"))
      (node (ref "T1") (pin "2") (pinfunction "2_2") (pintype "passive"))
      (node (ref "U3") (pin "48") (pinfunction "VDDRX_48") (pintype "passive"))
      (node (ref "U3") (pin "49") (pinfunction "VDDTX_49") (pintype "passive"))
      (node (ref "U3") (pin "54") (pinfunction "VDDPLL_54") (pintype "passive"))
    )
    (net (code "59") (name "TD_N") (class "Default")
      (node (ref "D5") (pin "2") (pinfunction "I/O1_2") (pintype "bidirectional"))
      (node (ref "L5") (pin "2") (pinfunction "2_2") (pintype "passive"))
      (node (ref "R32") (pin "1") (pinfunction "1_1") (pintype "passive"))
      (node (ref "R5") (pin "2") (pinfunction "2_2") (pintype "passive"))
    )
    (net (code "60") (name "TD_P") (class "Default")
      (node (ref "D5") (pin "3") (pinfunction "I/O2_3") (pintype "bidirectional"))
      (node (ref "L4") (pin "2") (pinfunction "2_2") (pintype "passive"))
      (node (ref "R31") (pin "1") (pinfunction "1_1") (pintype "passive"))
      (node (ref "R6") (pin "2") (pinfunction "2_2") (pintype "passive"))
    )
    (net (code "61") (name "TXD") (class "Default")
      (node (ref "R24") (pin "2") (pinfunction "2_2") (pintype "passive"))
      (node (ref "U3") (pin "31") (pinfunction "RC6/TX1/CK1_31") (pintype "passive"))
      (node (ref "U5") (pin "2") (pinfunction "I_2") (pintype "input"))
    )
    (net (code "62") (name "TXOUT") (class "Default")
      (node (ref "J4") (pin "1") (pinfunction "1_1") (pintype "passive"))
      (node (ref "R24") (pin "1") (pinfunction "1_1") (pintype "passive"))
    )
    (net (code "63") (name "TX_CT") (class "Default")
      (node (ref "BR1") (pin "AC1") (pinfunction "AC1_AC1") (pintype "passive"))
      (node (ref "C3") (pin "1") (pinfunction "1_1") (pintype "passive"))
      (node (ref "T1") (pin "15") (pinfunction "15_15") (pintype "passive"))
    )
    (net (code "64") (name "TX_N") (class "Default")
      (node (ref "J1") (pin "2") (pinfunction "2_2") (pintype "passive"))
      (node (ref "T1") (pin "14") (pinfunction "14_14") (pintype "passive"))
    )
    (net (code "65") (name "TX_P") (class "Default")
      (node (ref "J1") (pin "1") (pinfunction "1_1") (pintype "passive"))
      (node (ref "T1") (pin "16") (pinfunction "16_16") (pintype "passive"))
    )
    (net (code "66") (name "VNNIN") (class "Default")
      (node (ref "C10") (pin "2") (pinfunction "2_2") (pintype "passive"))
      (node (ref "C8") (pin "2") (pinfunction "2_2") (pintype "passive"))
      (node (ref "D1") (pin "A") (pinfunction "A_A") (pintype "passive"))
      (node (ref "D2") (pin "C") (pinfunction "C_C") (pintype "passive"))
      (node (ref "L2") (pin "2") (pinfunction "2_2") (pintype "passive"))
      (node (ref "PS1") (pin "2") (pinfunction "VIN-_2") (pintype "bidirectional"))
      (node (ref "TP3") (pin "1") (pinfunction "P$1_1") (pintype "bidirectional"))
    )
    (net (code "67") (name "VPPIN") (class "Default")
      (node (ref "C35") (pin "2") (pinfunction "2_2") (pintype "passive"))
      (node (ref "C8") (pin "1") (pinfunction "1_1") (pintype "passive"))
      (node (ref "D1") (pin "C") (pinfunction "C_C") (pintype "passive"))
      (node (ref "L1") (pin "2") (pinfunction "2_2") (pintype "passive"))
      (node (ref "PS1") (pin "1") (pinfunction "VIN+_1") (pintype "bidirectional"))
      (node (ref "R13") (pin "1") (pinfunction "1_1") (pintype "passive"))
      (node (ref "TP2") (pin "1") (pinfunction "P$1_1") (pintype "bidirectional"))
      (node (ref "U2") (pin "1") (pinfunction "ANODE_1") (pintype "passive"))
    )
    (net (code "68") (name "unconnected-(J3-LVP-Pad6)") (class "Default")
      (node (ref "J3") (pin "6") (pinfunction "LVP_6") (pintype "bidirectional"))
    )
    (net (code "69") (name "unconnected-(OSC1-NC-Pad2)") (class "Default")
      (node (ref "OSC1") (pin "2") (pinfunction "NC_2") (pintype "bidirectional"))
    )
    (net (code "70") (name "unconnected-(PS1-ADJ-Pad9)") (class "Default")
      (node (ref "PS1") (pin "9") (pinfunction "ADJ_9") (pintype "bidirectional"))
    )
    (net (code "71") (name "unconnected-(PS1-NC-Pad4)") (class "Default")
      (node (ref "PS1") (pin "4") (pinfunction "NC_4") (pintype "bidirectional"))
    )
    (net (code "72") (name "unconnected-(PS1-NC-Pad5)") (class "Default")
      (node (ref "PS1") (pin "5") (pinfunction "NC_5") (pintype "bidirectional"))
    )
    (net (code "73") (name "unconnected-(PS1-NC-Pad6)") (class "Default")
      (node (ref "PS1") (pin "6") (pinfunction "NC_6") (pintype "bidirectional"))
    )
    (net (code "74") (name "unconnected-(T1-Pad4)") (class "Default")
      (node (ref "T1") (pin "4") (pinfunction "4_4") (pintype "passive"))
    )
    (net (code "75") (name "unconnected-(T1-Pad5)") (class "Default")
      (node (ref "T1") (pin "5") (pinfunction "5_5") (pintype "passive"))
    )
    (net (code "76") (name "unconnected-(T1-Pad12)") (class "Default")
      (node (ref "T1") (pin "12") (pinfunction "12_12") (pintype "passive"))
    )
    (net (code "77") (name "unconnected-(T1-Pad13)") (class "Default")
      (node (ref "T1") (pin "13") (pinfunction "13_13") (pintype "passive"))
    )
    (net (code "78") (name "unconnected-(U1-BIAS-Pad2)") (class "Default")
      (node (ref "U1") (pin "2") (pinfunction "BIAS_2") (pintype "bidirectional"))
    )
    (net (code "79") (name "unconnected-(U3-OSC2{slash}CLKO-Pad40)") (class "Default")
      (node (ref "U3") (pin "40") (pinfunction "OSC2/CLKO_40") (pintype "passive"))
    )
    (net (code "80") (name "unconnected-(U3-RA2{slash}AN2{slash}VREF--Pad22)") (class "Default")
      (node (ref "U3") (pin "22") (pinfunction "RA2/AN2/VREF-_22") (pintype "passive"))
    )
    (net (code "81") (name "unconnected-(U3-RA3{slash}AN3{slash}VREF+-Pad21)") (class "Default")
      (node (ref "U3") (pin "21") (pinfunction "RA3/AN3/VREF+_21") (pintype "passive"))
    )
    (net (code "82") (name "unconnected-(U3-RA4{slash}T0CKI-Pad28)") (class "Default")
      (node (ref "U3") (pin "28") (pinfunction "RA4/T0CKI_28") (pintype "passive"))
    )
    (net (code "83") (name "unconnected-(U3-RA5{slash}AN4-Pad27)") (class "Default")
      (node (ref "U3") (pin "27") (pinfunction "RA5/AN4_27") (pintype "passive"))
    )
    (net (code "84") (name "unconnected-(U3-RB3{slash}INT3-Pad6)") (class "Default")
      (node (ref "U3") (pin "6") (pinfunction "RB3/INT3_6") (pintype "passive"))
    )
    (net (code "85") (name "unconnected-(U3-RB5{slash}KBI1-Pad43)") (class "Default")
      (node (ref "U3") (pin "43") (pinfunction "RB5/KBI1_43") (pintype "passive"))
    )
    (net (code "86") (name "unconnected-(U3-RC0{slash}T1OSO{slash}T13CKI-Pad30)") (class "Default")
      (node (ref "U3") (pin "30") (pinfunction "RC0/T1OSO/T13CKI_30") (pintype "passive"))
    )
    (net (code "87") (name "unconnected-(U3-RC1{slash}T1OSI{slash}ECCP2{slash}P2A-Pad29)") (class "Default")
      (node (ref "U3") (pin "29") (pinfunction "RC1/T1OSI/ECCP2/P2A_29") (pintype "passive"))
    )
    (net (code "88") (name "unconnected-(U3-RC2{slash}ECCP1{slash}P1A-Pad33)") (class "Default")
      (node (ref "U3") (pin "33") (pinfunction "RC2/ECCP1/P1A_33") (pintype "passive"))
    )
    (net (code "89") (name "unconnected-(U3-RD0{slash}P1B-Pad60)") (class "Default")
      (node (ref "U3") (pin "60") (pinfunction "RD0/P1B_60") (pintype "passive"))
    )
    (net (code "90") (name "unconnected-(U3-RD1{slash}ECCP3{slash}P3A-Pad59)") (class "Default")
      (node (ref "U3") (pin "59") (pinfunction "RD1/ECCP3/P3A_59") (pintype "passive"))
    )
    (net (code "91") (name "unconnected-(U3-RD2{slash}CCP4{slash}P3D-Pad58)") (class "Default")
      (node (ref "U3") (pin "58") (pinfunction "RD2/CCP4/P3D_58") (pintype "passive"))
    )
    (net (code "92") (name "unconnected-(U3-RE0{slash}P2D-Pad2)") (class "Default")
      (node (ref "U3") (pin "2") (pinfunction "RE0/P2D_2") (pintype "passive"))
    )
    (net (code "93") (name "unconnected-(U3-RE1{slash}P2C-Pad1)") (class "Default")
      (node (ref "U3") (pin "1") (pinfunction "RE1/P2C_1") (pintype "passive"))
    )
    (net (code "94") (name "unconnected-(U3-RE2{slash}P2B-Pad64)") (class "Default")
      (node (ref "U3") (pin "64") (pinfunction "RE2/P2B_64") (pintype "passive"))
    )
    (net (code "95") (name "unconnected-(U3-RE3{slash}P3C-Pad63)") (class "Default")
      (node (ref "U3") (pin "63") (pinfunction "RE3/P3C_63") (pintype "passive"))
    )
    (net (code "96") (name "unconnected-(U3-RF1{slash}AN6{slash}C2OUT-Pad17)") (class "Default")
      (node (ref "U3") (pin "17") (pinfunction "RF1/AN6/C2OUT_17") (pintype "passive"))
    )
    (net (code "97") (name "unconnected-(U3-RF2{slash}AN7{slash}C1OUT-Pad16)") (class "Default")
      (node (ref "U3") (pin "16") (pinfunction "RF2/AN7/C1OUT_16") (pintype "passive"))
    )
    (net (code "98") (name "unconnected-(U3-RF3{slash}AN8-Pad15)") (class "Default")
      (node (ref "U3") (pin "15") (pinfunction "RF3/AN8_15") (pintype "passive"))
    )
    (net (code "99") (name "unconnected-(U3-RF4{slash}AN9-Pad14)") (class "Default")
      (node (ref "U3") (pin "14") (pinfunction "RF4/AN9_14") (pintype "passive"))
    )
    (net (code "100") (name "unconnected-(U3-RF5{slash}AN10{slash}CVREF-Pad13)") (class "Default")
      (node (ref "U3") (pin "13") (pinfunction "RF5/AN10/CVREF_13") (pintype "passive"))
    )
    (net (code "101") (name "unconnected-(U3-RF6{slash}AN11-Pad12)") (class "Default")
      (node (ref "U3") (pin "12") (pinfunction "RF6/AN11_12") (pintype "passive"))
    )
    (net (code "102") (name "unconnected-(U3-RF7{slash}~{SS1}-Pad11)") (class "Default")
      (node (ref "U3") (pin "11") (pinfunction "RF7/~{SS1}_11") (pintype "passive"))
    )
    (net (code "103") (name "unconnected-(U3-RG4{slash}CCP5{slash}P1D-Pad8)") (class "Default")
      (node (ref "U3") (pin "8") (pinfunction "RG4/CCP5/P1D_8") (pintype "passive"))
    )
    (net (code "104") (name "{slash}MCLR") (class "Default")
      (node (ref "J3") (pin "1") (pinfunction "VPP/MCLR_1") (pintype "passive"))
      (node (ref "R28") (pin "2") (pinfunction "2_2") (pintype "passive"))
      (node (ref "U3") (pin "7") (pinfunction "~{MCLR}_7") (pintype "passive"))
    )
  )
)
